# Trabajo.net
KiCad netlist of a schematic drawn in EAGLE
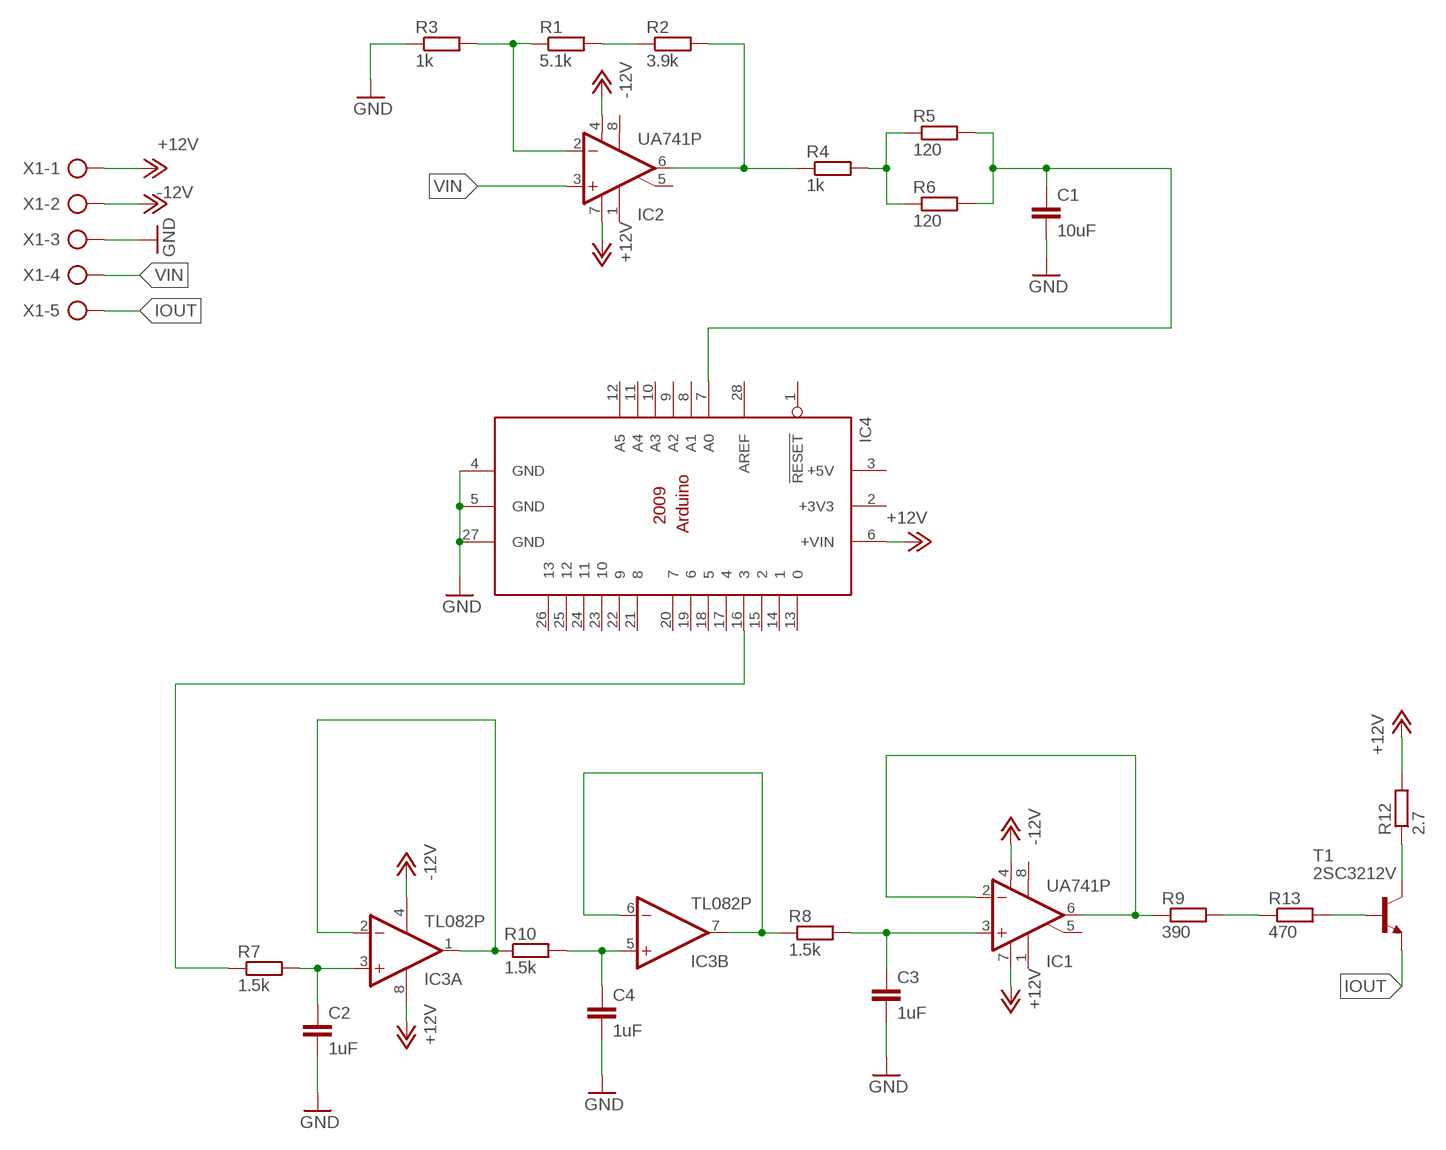
[diagram p0: schematic, sheet 1]

(export (version "E")
  (design (tool "Eeschema 10.0.6"))
  (components
    (comp (ref "C1")
      (value "10uF")
      (footprint "eagle-import:C025-024X044")
      (libsource (lib "eagle-import") (part "C-EU025-024X044"))
    )
    (comp (ref "C2")
      (value "1uF")
      (footprint "eagle-import:C025-024X044")
      (libsource (lib "eagle-import") (part "C-EU025-024X044"))
    )
    (comp (ref "C3")
      (value "1uF")
      (footprint "eagle-import:C025-024X044")
      (libsource (lib "eagle-import") (part "C-EU025-024X044"))
    )
    (comp (ref "C4")
      (value "1uF")
      (footprint "eagle-import:C025-024X044")
      (libsource (lib "eagle-import") (part "C-EU025-024X044"))
    )
    (comp (ref "IC1")
      (value "UA741P")
      (footprint "eagle-import:DIL08")
      (libsource (lib "eagle-import") (part "741PUA"))
    )
    (comp (ref "IC2")
      (value "UA741P")
      (footprint "eagle-import:DIL08")
      (libsource (lib "eagle-import") (part "741PUA"))
    )
    (comp (ref "IC3")
      (value "TL082P")
      (footprint "eagle-import:DIL08")
      (libsource (lib "eagle-import") (part "TL082P"))
    )
    (comp (ref "IC4")
      (value "ARDUINO2009_10")
      (footprint "eagle-import:ARDUINO2009")
      (libsource (lib "eagle-import") (part "ARDUINO2009_10"))
    )
    (comp (ref "R1")
      (value "5.1k")
      (footprint "eagle-import:0204_7")
      (libsource (lib "eagle-import") (part "R-EU_0204/7"))
    )
    (comp (ref "R2")
      (value "3.9k")
      (footprint "eagle-import:0204_7")
      (libsource (lib "eagle-import") (part "R-EU_0204/7"))
    )
    (comp (ref "R3")
      (value "1k")
      (footprint "eagle-import:0204_7")
      (libsource (lib "eagle-import") (part "R-EU_0204/7"))
    )
    (comp (ref "R4")
      (value "1k")
      (footprint "eagle-import:0204_7")
      (libsource (lib "eagle-import") (part "R-EU_0204/7"))
    )
    (comp (ref "R5")
      (value "120")
      (footprint "eagle-import:0204_7")
      (libsource (lib "eagle-import") (part "R-EU_0204/7"))
    )
    (comp (ref "R6")
      (value "120")
      (footprint "eagle-import:0204_7")
      (libsource (lib "eagle-import") (part "R-EU_0204/7"))
    )
    (comp (ref "R7")
      (value "1.5k")
      (footprint "eagle-import:0204_7")
      (libsource (lib "eagle-import") (part "R-EU_0204/7"))
    )
    (comp (ref "R8")
      (value "1.5k")
      (footprint "eagle-import:0204_7")
      (libsource (lib "eagle-import") (part "R-EU_0204/7"))
    )
    (comp (ref "R9")
      (value "390")
      (footprint "eagle-import:0204_7")
      (libsource (lib "eagle-import") (part "R-EU_0204/7"))
    )
    (comp (ref "R10")
      (value "1.5k")
      (footprint "eagle-import:0204_7")
      (libsource (lib "eagle-import") (part "R-EU_0204/7"))
    )
    (comp (ref "R12")
      (value "2.7")
      (footprint "eagle-import:0204_7")
      (libsource (lib "eagle-import") (part "R-EU_0204/7"))
    )
    (comp (ref "R13")
      (value "470")
      (footprint "eagle-import:0204_7")
      (libsource (lib "eagle-import") (part "R-EU_0204/7"))
    )
    (comp (ref "T1")
      (value "2SC3212V")
      (footprint "eagle-import:TO220AV")
      (libsource (lib "eagle-import") (part "2SC3212V"))
    )
    (comp (ref "X1")
      (value "AK300/5")
      (footprint "eagle-import:AK300_5")
      (libsource (lib "eagle-import") (part "AK300/5"))
    )
  )
  (nets
    (net (code "1") (name "+12V") (class "Default")
      (node (ref "IC1") (pin "7") (pinfunction "V+_7") (pintype "power_in"))
      (node (ref "IC2") (pin "7") (pinfunction "V+_7") (pintype "power_in"))
      (node (ref "IC3") (pin "8") (pinfunction "V+_8") (pintype "power_in"))
      (node (ref "IC4") (pin "6") (pinfunction "+VIN_6") (pintype "bidirectional"))
      (node (ref "R12") (pin "2") (pinfunction "2_2") (pintype "passive"))
      (node (ref "X1") (pin "1") (pinfunction "KL_1") (pintype "passive"))
    )
    (net (code "2") (name "-12V") (class "Default")
      (node (ref "IC1") (pin "4") (pinfunction "V-_4") (pintype "power_in"))
      (node (ref "IC2") (pin "4") (pinfunction "V-_4") (pintype "power_in"))
      (node (ref "IC3") (pin "4") (pinfunction "V-_4") (pintype "power_in"))
      (node (ref "X1") (pin "2") (pinfunction "KL_2") (pintype "passive"))
    )
    (net (code "3") (name "/+3V3") (class "Default")
      (node (ref "IC4") (pin "2") (pinfunction "+3V3_2") (pintype "power_in"))
    )
    (net (code "4") (name "/+5V") (class "Default")
      (node (ref "IC4") (pin "3") (pinfunction "+5V_3") (pintype "power_in"))
    )
    (net (code "5") (name "GND") (class "Default")
      (node (ref "C1") (pin "2") (pinfunction "2_2") (pintype "passive"))
      (node (ref "C2") (pin "2") (pinfunction "2_2") (pintype "passive"))
      (node (ref "C3") (pin "2") (pinfunction "2_2") (pintype "passive"))
      (node (ref "C4") (pin "2") (pinfunction "2_2") (pintype "passive"))
      (node (ref "IC4") (pin "27") (pinfunction "GND_27") (pintype "power_in"))
      (node (ref "IC4") (pin "4") (pinfunction "GND_4") (pintype "power_in"))
      (node (ref "IC4") (pin "5") (pinfunction "GND_5") (pintype "power_in"))
      (node (ref "R3") (pin "1") (pinfunction "1_1") (pintype "passive"))
      (node (ref "X1") (pin "3") (pinfunction "KL_3") (pintype "passive"))
    )
    (net (code "6") (name "IOUT") (class "Default")
      (node (ref "T1") (pin "3") (pinfunction "E_3") (pintype "passive"))
      (node (ref "X1") (pin "5") (pinfunction "KL_5") (pintype "passive"))
    )
    (net (code "7") (name "Net-(IC1-+IN)") (class "Default")
      (node (ref "C3") (pin "1") (pinfunction "1_1") (pintype "passive"))
      (node (ref "IC1") (pin "3") (pinfunction "+IN_3") (pintype "input"))
      (node (ref "R8") (pin "2") (pinfunction "2_2") (pintype "passive"))
    )
    (net (code "8") (name "Net-(IC1--IN)") (class "Default")
      (node (ref "IC1") (pin "2") (pinfunction "-IN_2") (pintype "input"))
      (node (ref "IC1") (pin "6") (pinfunction "OUT_6") (pintype "output"))
      (node (ref "R9") (pin "1") (pinfunction "1_1") (pintype "passive"))
    )
    (net (code "9") (name "Net-(IC2--IN)") (class "Default")
      (node (ref "IC2") (pin "2") (pinfunction "-IN_2") (pintype "input"))
      (node (ref "R1") (pin "1") (pinfunction "1_1") (pintype "passive"))
      (node (ref "R3") (pin "2") (pinfunction "2_2") (pintype "passive"))
    )
    (net (code "10") (name "Net-(IC2-OUT)") (class "Default")
      (node (ref "IC2") (pin "6") (pinfunction "OUT_6") (pintype "output"))
      (node (ref "R2") (pin "2") (pinfunction "2_2") (pintype "passive"))
      (node (ref "R4") (pin "1") (pinfunction "1_1") (pintype "passive"))
    )
    (net (code "11") (name "Net-(IC3A-+IN)") (class "Default")
      (node (ref "C2") (pin "1") (pinfunction "1_1") (pintype "passive"))
      (node (ref "IC3") (pin "3") (pinfunction "+IN_3") (pintype "input"))
      (node (ref "R7") (pin "2") (pinfunction "2_2") (pintype "passive"))
    )
    (net (code "12") (name "Net-(IC3A--IN)") (class "Default")
      (node (ref "IC3") (pin "1") (pinfunction "OUT_1") (pintype "output"))
      (node (ref "IC3") (pin "2") (pinfunction "-IN_2") (pintype "input"))
      (node (ref "R10") (pin "1") (pinfunction "1_1") (pintype "passive"))
    )
    (net (code "13") (name "Net-(IC3B-+IN)") (class "Default")
      (node (ref "C4") (pin "1") (pinfunction "1_1") (pintype "passive"))
      (node (ref "IC3") (pin "5") (pinfunction "+IN_5") (pintype "input"))
      (node (ref "R10") (pin "2") (pinfunction "2_2") (pintype "passive"))
    )
    (net (code "14") (name "Net-(IC3B--IN)") (class "Default")
      (node (ref "IC3") (pin "6") (pinfunction "-IN_6") (pintype "input"))
      (node (ref "IC3") (pin "7") (pinfunction "OUT_7") (pintype "output"))
      (node (ref "R8") (pin "1") (pinfunction "1_1") (pintype "passive"))
    )
    (net (code "15") (name "Net-(IC4-3)") (class "Default")
      (node (ref "IC4") (pin "16") (pinfunction "3_16") (pintype "bidirectional"))
      (node (ref "R7") (pin "1") (pinfunction "1_1") (pintype "passive"))
    )
    (net (code "16") (name "Net-(IC4-A0)") (class "Default")
      (node (ref "C1") (pin "1") (pinfunction "1_1") (pintype "passive"))
      (node (ref "IC4") (pin "7") (pinfunction "A0_7") (pintype "bidirectional"))
      (node (ref "R5") (pin "2") (pinfunction "2_2") (pintype "passive"))
      (node (ref "R6") (pin "2") (pinfunction "2_2") (pintype "passive"))
    )
    (net (code "17") (name "Net-(R1-Pad2)") (class "Default")
      (node (ref "R1") (pin "2") (pinfunction "2_2") (pintype "passive"))
      (node (ref "R2") (pin "1") (pinfunction "1_1") (pintype "passive"))
    )
    (net (code "18") (name "Net-(R4-Pad2)") (class "Default")
      (node (ref "R4") (pin "2") (pinfunction "2_2") (pintype "passive"))
      (node (ref "R5") (pin "1") (pinfunction "1_1") (pintype "passive"))
      (node (ref "R6") (pin "1") (pinfunction "1_1") (pintype "passive"))
    )
    (net (code "19") (name "Net-(R13-Pad1)") (class "Default")
      (node (ref "R13") (pin "1") (pinfunction "1_1") (pintype "passive"))
      (node (ref "R9") (pin "2") (pinfunction "2_2") (pintype "passive"))
    )
    (net (code "20") (name "Net-(T1-B)") (class "Default")
      (node (ref "R13") (pin "2") (pinfunction "2_2") (pintype "passive"))
      (node (ref "T1") (pin "1") (pinfunction "B_1") (pintype "passive"))
    )
    (net (code "21") (name "Net-(T1-C)") (class "Default")
      (node (ref "R12") (pin "1") (pinfunction "1_1") (pintype "passive"))
      (node (ref "T1") (pin "2") (pinfunction "C_2") (pintype "passive"))
    )
    (net (code "22") (name "VIN") (class "Default")
      (node (ref "IC2") (pin "3") (pinfunction "+IN_3") (pintype "input"))
      (node (ref "X1") (pin "4") (pinfunction "KL_4") (pintype "passive"))
    )
    (net (code "23") (name "unconnected-(IC1-ON1-Pad1)") (class "Default")
      (node (ref "IC1") (pin "1") (pinfunction "ON1_1") (pintype "passive"))
    )
    (net (code "24") (name "unconnected-(IC1-ON2-Pad5)") (class "Default")
      (node (ref "IC1") (pin "5") (pinfunction "ON2_5") (pintype "passive"))
    )
    (net (code "25") (name "unconnected-(IC1-OPT-Pad8)") (class "Default")
      (node (ref "IC1") (pin "8") (pinfunction "OPT_8") (pintype "passive"))
    )
    (net (code "26") (name "unconnected-(IC2-ON1-Pad1)") (class "Default")
      (node (ref "IC2") (pin "1") (pinfunction "ON1_1") (pintype "passive"))
    )
    (net (code "27") (name "unconnected-(IC2-ON2-Pad5)") (class "Default")
      (node (ref "IC2") (pin "5") (pinfunction "ON2_5") (pintype "passive"))
    )
    (net (code "28") (name "unconnected-(IC2-OPT-Pad8)") (class "Default")
      (node (ref "IC2") (pin "8") (pinfunction "OPT_8") (pintype "passive"))
    )
    (net (code "29") (name "unconnected-(IC4-0-Pad13)") (class "Default")
      (node (ref "IC4") (pin "13") (pinfunction "0_13") (pintype "bidirectional"))
    )
    (net (code "30") (name "unconnected-(IC4-1-Pad14)") (class "Default")
      (node (ref "IC4") (pin "14") (pinfunction "1_14") (pintype "bidirectional"))
    )
    (net (code "31") (name "unconnected-(IC4-2-Pad15)") (class "Default")
      (node (ref "IC4") (pin "15") (pinfunction "2_15") (pintype "bidirectional"))
    )
    (net (code "32") (name "unconnected-(IC4-4-Pad17)") (class "Default")
      (node (ref "IC4") (pin "17") (pinfunction "4_17") (pintype "bidirectional"))
    )
    (net (code "33") (name "unconnected-(IC4-5-Pad18)") (class "Default")
      (node (ref "IC4") (pin "18") (pinfunction "5_18") (pintype "bidirectional"))
    )
    (net (code "34") (name "unconnected-(IC4-6-Pad19)") (class "Default")
      (node (ref "IC4") (pin "19") (pinfunction "6_19") (pintype "bidirectional"))
    )
    (net (code "35") (name "unconnected-(IC4-7-Pad20)") (class "Default")
      (node (ref "IC4") (pin "20") (pinfunction "7_20") (pintype "bidirectional"))
    )
    (net (code "36") (name "unconnected-(IC4-8-Pad21)") (class "Default")
      (node (ref "IC4") (pin "21") (pinfunction "8_21") (pintype "bidirectional"))
    )
    (net (code "37") (name "unconnected-(IC4-9-Pad22)") (class "Default")
      (node (ref "IC4") (pin "22") (pinfunction "9_22") (pintype "bidirectional"))
    )
    (net (code "38") (name "unconnected-(IC4-10-Pad23)") (class "Default")
      (node (ref "IC4") (pin "23") (pinfunction "10_23") (pintype "bidirectional"))
    )
    (net (code "39") (name "unconnected-(IC4-11-Pad24)") (class "Default")
      (node (ref "IC4") (pin "24") (pinfunction "11_24") (pintype "bidirectional"))
    )
    (net (code "40") (name "unconnected-(IC4-12-Pad25)") (class "Default")
      (node (ref "IC4") (pin "25") (pinfunction "12_25") (pintype "bidirectional"))
    )
    (net (code "41") (name "unconnected-(IC4-13-Pad26)") (class "Default")
      (node (ref "IC4") (pin "26") (pinfunction "13_26") (pintype "bidirectional"))
    )
    (net (code "42") (name "unconnected-(IC4-A1-Pad8)") (class "Default")
      (node (ref "IC4") (pin "8") (pinfunction "A1_8") (pintype "bidirectional"))
    )
    (net (code "43") (name "unconnected-(IC4-A2-Pad9)") (class "Default")
      (node (ref "IC4") (pin "9") (pinfunction "A2_9") (pintype "bidirectional"))
    )
    (net (code "44") (name "unconnected-(IC4-A3-Pad10)") (class "Default")
      (node (ref "IC4") (pin "10") (pinfunction "A3_10") (pintype "bidirectional"))
    )
    (net (code "45") (name "unconnected-(IC4-A4-Pad11)") (class "Default")
      (node (ref "IC4") (pin "11") (pinfunction "A4_11") (pintype "bidirectional"))
    )
    (net (code "46") (name "unconnected-(IC4-A5-Pad12)") (class "Default")
      (node (ref "IC4") (pin "12") (pinfunction "A5_12") (pintype "bidirectional"))
    )
    (net (code "47") (name "unconnected-(IC4-AREF-Pad28)") (class "Default")
      (node (ref "IC4") (pin "28") (pinfunction "AREF_28") (pintype "bidirectional"))
    )
    (net (code "48") (name "unconnected-(IC4-~{RESET}-Pad1)") (class "Default")
      (node (ref "IC4") (pin "1") (pinfunction "~{RESET}_1") (pintype "bidirectional"))
    )
  )
)
